# 05-PMC.net
KiCad netlist of a schematic drawn in Altium Designer
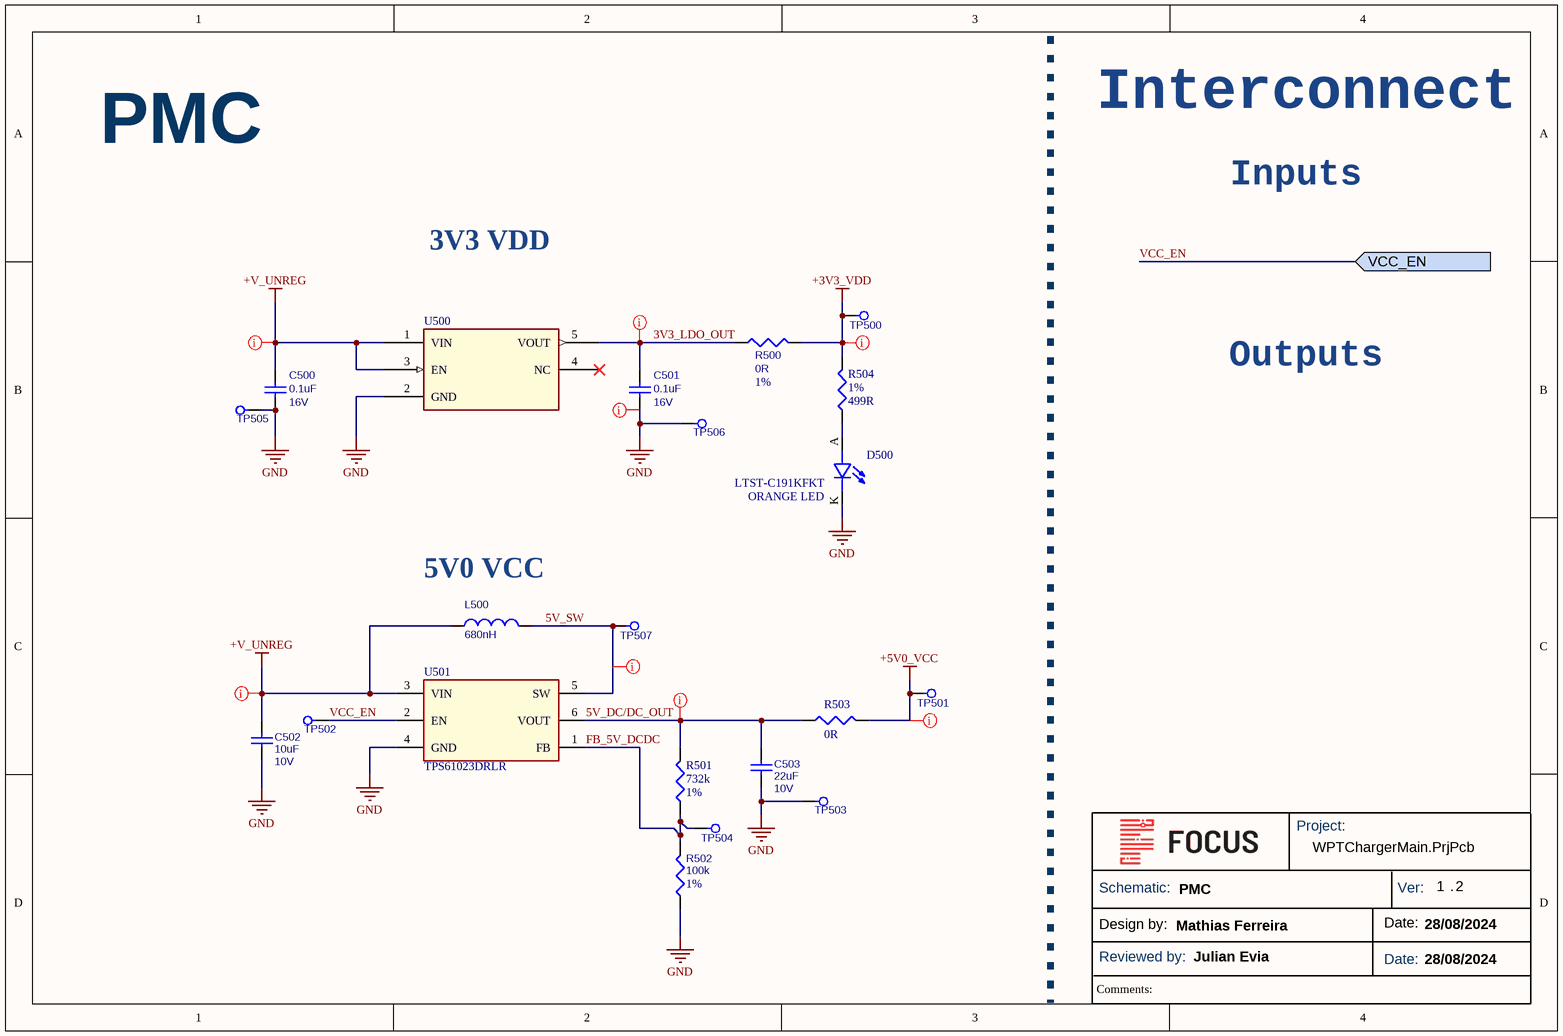
[diagram p0: 05-PMC.SchDoc]

(export (version "E")
  (design (tool "Eeschema 10.0.6"))
  (components
    (comp (ref "C500")
      (value "0.1uF")
      (footprint "C0402")
      (description "Capacitor, 0.1uF, X7R, 16V, 10%, 0402, Implant-grade")
      (fields
        (field (name "MANUFACTURER") "Murata")
        (field (name "MANUFACTURER PART NUMBER") "GCM155R71C104KA55")
        (field (name "RATING") "16V")
      )
      (libsource (lib "MP-LIBRARY") (part "GCM155R71C104KA55"))
    )
    (comp (ref "C501")
      (value "0.1uF")
      (footprint "C0402")
      (description "Capacitor, 0.1uF, X7R, 16V, 10%, 0402, Implant-grade")
      (fields
        (field (name "MANUFACTURER") "Murata")
        (field (name "MANUFACTURER PART NUMBER") "GCM155R71C104KA55")
        (field (name "RATING") "16V")
      )
      (libsource (lib "MP-LIBRARY") (part "GCM155R71C104KA55"))
    )
    (comp (ref "C502")
      (value "10uF")
      (footprint "C0402")
      (description "Capacitor, 10uf, X5R, 10V, 20%, 0402, Implant-grade")
      (fields
        (field (name "MANUFACTURER") "Murata")
        (field (name "MANUFACTURER PART NUMBER") "ZRB15XR61A106ME01D")
        (field (name "RATING") "10V")
      )
      (libsource (lib "MP-LIBRARY") (part "ZRB15XR61A106ME01D"))
    )
    (comp (ref "C503")
      (value "22uF")
      (footprint "C0603")
      (description "22 µF ±20% 10V Ceramic Capacitor X5R 0603 (1608 Metric)")
      (fields
        (field (name "MANUFACTURER") "Murata")
        (field (name "MANUFACTURER PART NUMBER") "GRM188R61A226ME15D")
        (field (name "RATING") "10V")
      )
      (libsource (lib "MP-LIBRARY") (part "GRM188R61A226ME15D"))
    )
    (comp (ref "D500")
      (value "LTST-C191KFKT")
      (footprint "LEDC0603")
      (description "LED, ORANGE, SMD, 0603, 2V, 30mA")
      (fields (field (name "MANUFACTURER") "Lite-On Inc.") (field (name "ALTIUM_VALUE") "ORANGE LED"))
      (libsource (lib "MP-LIBRARY") (part "LED ORANGE CLEAR SMD 0603"))
    )
    (comp (ref "L500")
      (value "680nH")
      (footprint "XAL4020-401MEC")
      (description "680 nH Shielded Molded Inductor 8.1 A 10.1mOhm Max 1616 (4040 Metric)")
      (fields
        (field (name "MANUFACTURER PART NUMBER") "XGL4015-681MEC")
        (field (name "MANUFACTURER") "Coilcraft")
      )
      (libsource (lib "MP-LIBRARY") (part "XGL4015-681MEC"))
    )
    (comp (ref "R500")
      (value "0R")
      (footprint "R0402")
      (description "Resistor, Zero ohms, 40V, 40mW, 1%, 0402, Implant-grade")
      (fields
        (field (name "MANUFACTURER") "Panasonic")
        (field (name "TOLERANCE") "1%")
        (field (name "MANUFACTURER PART NUMBER") "ERJ-2GE0R00X")
      )
      (libsource (lib "MP-LIBRARY") (part "ERJ-2GE0R00X"))
    )
    (comp (ref "R501")
      (value "732k")
      (footprint "R0402")
      (description "732 kOhms ±1% 0.063W, 1/16W Chip Resistor 0402 (1005 Metric) Automotive AEC-Q200 Thick Film")
      (fields
        (field (name "POWER") "63mW")
        (field (name "MANUFACTURER") "Vishay Dale")
        (field (name "TOLERANCE") "1%")
      )
      (libsource (lib "MP-LIBRARY") (part "CRCW0402732KFKED"))
    )
    (comp (ref "R502")
      (value "100k")
      (footprint "R0402")
      (description "Resistor, 100k, 1%, 0402, Implant-grade")
      (fields
        (field (name "MANUFACTURER") "Panasonic")
        (field (name "TOLERANCE") "1%")
        (field (name "MANUFACTURER PART NUMBER") "ERJ-2RKF1003X")
      )
      (libsource (lib "MP-LIBRARY") (part "ERJ-2RKF1003X"))
    )
    (comp (ref "R503")
      (value "0R")
      (footprint "R0805")
      (description "0 Ohms Jumper Chip Resistor 0805 (2012 Metric) Automotive AEC-Q200, Pulse Withstanding Thick Film")
      (fields
        (field (name "MANUFACTURER") "Vishay Dale")
        (field (name "MANUFACTURER PART NUMBER") "RCS08050000Z0EA")
      )
      (libsource (lib "MP-LIBRARY") (part "RCS08050000Z0EA"))
    )
    (comp (ref "R504")
      (value "499R")
      (footprint "R0402")
      (fields
        (field (name "MANUFACTURER") "Vishay Dale")
        (field (name "MANUFACTURER PART NUMBER") "CRCW0402499RFKEDHP")
        (field (name "POWER") "200mW")
        (field (name "TOLERANCE") "1%")
      )
      (libsource (lib "MP-LIBRARY") (part "CRCW0402499RFKEDHP"))
    )
    (comp (ref "TP500")
      (value "Test Point")
      (footprint "testpad_0.9mm")
      (description "Test pad, 0.90mm circular pad")
      (libsource (lib "MP-LIBRARY") (part "Test Point"))
    )
    (comp (ref "TP501")
      (value "Test Point")
      (footprint "testpad_0.9mm")
      (description "Test pad, 0.90mm circular pad")
      (libsource (lib "MP-LIBRARY") (part "Test Point"))
    )
    (comp (ref "TP502")
      (value "Test Point")
      (footprint "testpad_0.9mm")
      (description "Test pad, 0.90mm circular pad")
      (libsource (lib "MP-LIBRARY") (part "Test Point"))
    )
    (comp (ref "TP503")
      (value "Test Point")
      (footprint "testpad_0.9mm")
      (description "Test pad, 0.90mm circular pad")
      (libsource (lib "MP-LIBRARY") (part "Test Point"))
    )
    (comp (ref "TP504")
      (value "Test Point")
      (footprint "testpad_0.9mm")
      (description "Test pad, 0.90mm circular pad")
      (libsource (lib "MP-LIBRARY") (part "Test Point"))
    )
    (comp (ref "TP505")
      (value "Test Point")
      (footprint "testpad_0.9mm")
      (description "Test pad, 0.90mm circular pad")
      (libsource (lib "MP-LIBRARY") (part "Test Point"))
    )
    (comp (ref "TP506")
      (value "Test Point")
      (footprint "testpad_0.9mm")
      (description "Test pad, 0.90mm circular pad")
      (libsource (lib "MP-LIBRARY") (part "Test Point"))
    )
    (comp (ref "TP507")
      (value "Test Point")
      (footprint "testpad_0.9mm")
      (description "Test pad, 0.90mm circular pad")
      (libsource (lib "MP-LIBRARY") (part "Test Point"))
    )
    (comp (ref "U500")
      (value "AP7354-33W5-7")
      (footprint "SOT25_AP7354_DIO-L")
      (description "Ldo, Fixed, 3.3V, 0.15A, -40 To 85Deg C Rohs Compliant: Yes")
      (fields (field (name "MANUFACTURER") "Diodes Inc"))
      (libsource (lib "MP-LIBRARY") (part "AP7354-33W5-7"))
    )
    (comp (ref "U501")
      (value "TPS61023DRLR")
      (footprint "DRL0006A")
      (description "Boost Switching Regulator IC Positive Adjustable 2.2V 1 Output 3A SOT-563, SOT-666")
      (fields (field (name "MANUFACTURER") "Texas Instruments"))
      (libsource (lib "MP-LIBRARY") (part "TPS61023DRLR"))
    )
  )
  (nets
    (net (code "1") (name "+3V3_VDD") (class "Default")
      (node (ref "R500") (pin "2") (pinfunction "2_2") (pintype "passive"))
      (node (ref "R504") (pin "2") (pinfunction "2_2") (pintype "passive"))
      (node (ref "TP500") (pin "1") (pinfunction "1_1") (pintype "passive"))
    )
    (net (code "2") (name "+5V0_VCC") (class "Default")
      (node (ref "R503") (pin "2") (pinfunction "2_2") (pintype "passive"))
      (node (ref "TP501") (pin "1") (pinfunction "1_1") (pintype "passive"))
    )
    (net (code "3") (name "+V_UNREG") (class "Default")
      (node (ref "C500") (pin "1") (pinfunction "1_1") (pintype "passive"))
      (node (ref "C502") (pin "2") (pinfunction "2_2") (pintype "passive"))
      (node (ref "L500") (pin "1") (pinfunction "1_1") (pintype "passive"))
      (node (ref "U500") (pin "1") (pinfunction "VIN_1") (pintype "power_in"))
      (node (ref "U500") (pin "3") (pinfunction "EN_3") (pintype "input"))
      (node (ref "U501") (pin "3") (pinfunction "VIN_3") (pintype "passive"))
    )
    (net (code "4") (name "/3V3_LDO_OUT") (class "Default")
      (node (ref "C501") (pin "1") (pinfunction "1_1") (pintype "passive"))
      (node (ref "R500") (pin "1") (pinfunction "1_1") (pintype "passive"))
      (node (ref "U500") (pin "5") (pinfunction "VOUT_5") (pintype "output"))
    )
    (net (code "5") (name "/5V_DC{slash}DC_OUT") (class "Default")
      (node (ref "C503") (pin "2") (pinfunction "2_2") (pintype "passive"))
      (node (ref "R501") (pin "2") (pinfunction "2_2") (pintype "passive"))
      (node (ref "R503") (pin "1") (pinfunction "1_1") (pintype "passive"))
      (node (ref "U501") (pin "6") (pinfunction "VOUT_6") (pintype "passive"))
    )
    (net (code "6") (name "/5V_SW") (class "Default")
      (node (ref "L500") (pin "2") (pinfunction "2_2") (pintype "passive"))
      (node (ref "TP507") (pin "1") (pinfunction "1_1") (pintype "passive"))
      (node (ref "U501") (pin "5") (pinfunction "SW_5") (pintype "passive"))
    )
    (net (code "7") (name "/FB_5V_DCDC") (class "Default")
      (node (ref "R501") (pin "1") (pinfunction "1_1") (pintype "passive"))
      (node (ref "R502") (pin "2") (pinfunction "2_2") (pintype "passive"))
      (node (ref "TP504") (pin "1") (pinfunction "1_1") (pintype "passive"))
      (node (ref "U501") (pin "1") (pinfunction "FB_1") (pintype "passive"))
    )
    (net (code "8") (name "/VCC_EN") (class "Default")
      (node (ref "TP502") (pin "1") (pinfunction "1_1") (pintype "passive"))
      (node (ref "U501") (pin "2") (pinfunction "EN_2") (pintype "passive"))
    )
    (net (code "9") (name "GND") (class "Default")
      (node (ref "C500") (pin "2") (pinfunction "2_2") (pintype "passive"))
      (node (ref "C501") (pin "2") (pinfunction "2_2") (pintype "passive"))
      (node (ref "C502") (pin "1") (pinfunction "1_1") (pintype "passive"))
      (node (ref "C503") (pin "1") (pinfunction "1_1") (pintype "passive"))
      (node (ref "D500") (pin "K") (pinfunction "K_K") (pintype "passive"))
      (node (ref "R502") (pin "1") (pinfunction "1_1") (pintype "passive"))
      (node (ref "TP503") (pin "1") (pinfunction "1_1") (pintype "passive"))
      (node (ref "TP505") (pin "1") (pinfunction "1_1") (pintype "passive"))
      (node (ref "TP506") (pin "1") (pinfunction "1_1") (pintype "passive"))
      (node (ref "U500") (pin "2") (pinfunction "GND_2") (pintype "passive"))
      (node (ref "U501") (pin "4") (pinfunction "GND_4") (pintype "passive"))
    )
    (net (code "10") (name "Net-(D500-PadA)") (class "Default")
      (node (ref "D500") (pin "A") (pinfunction "A_A") (pintype "passive"))
      (node (ref "R504") (pin "1") (pinfunction "1_1") (pintype "passive"))
    )
    (net (code "11") (name "unconnected-(U500-NC-Pad4)") (class "Default")
      (node (ref "U500") (pin "4") (pinfunction "NC_4") (pintype "passive+no_connect"))
    )
  )
)
